# Sheet2.net
KiCad netlist of a schematic drawn in Altium Designer
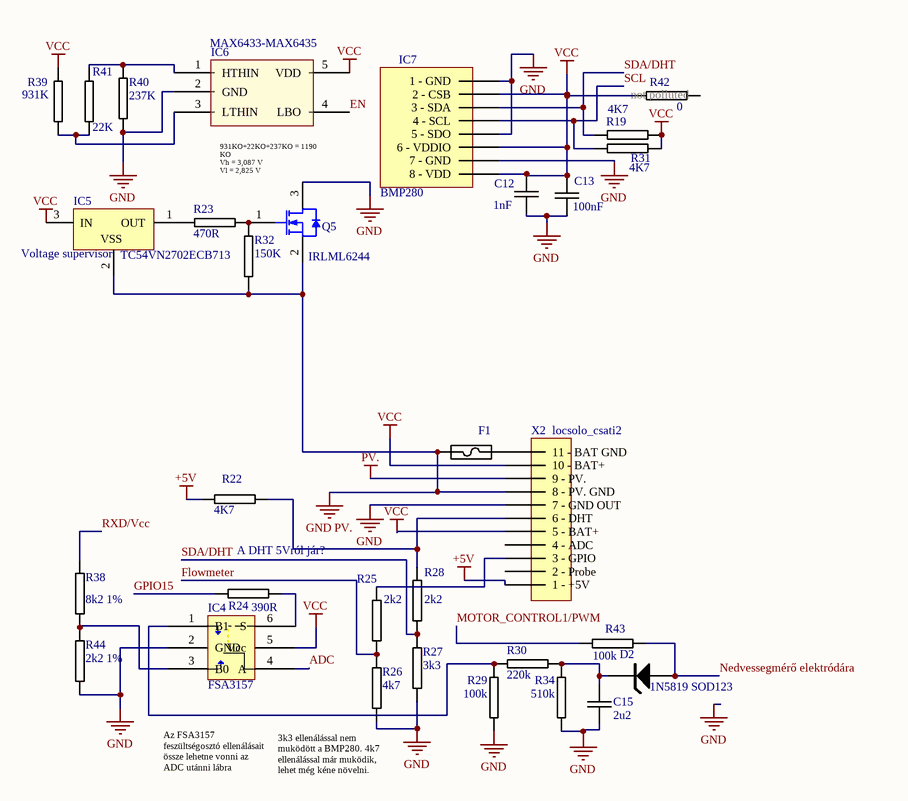
[diagram p0: Sheet2.SchDoc]

(export (version "E")
  (design (tool "Eeschema 10.0.6"))
  (components
    (comp (ref "C12")
      (value "1nF")
      (footprint "0805C-GENERIC")
      (description "100nF")
      (libsource (lib "vh_altium_library") (part "C0805-GENERIC"))
    )
    (comp (ref "C13")
      (value "100nF")
      (footprint "0805C-GENERIC")
      (libsource (lib "vh_altium_library") (part "C0805-GENERIC"))
    )
    (comp (ref "C15")
      (value "2u2")
      (footprint "0805C-GENERIC")
      (description "CAPACITOR 0805 CERAMIC")
      (fields
        (field (name "MANUFACTURER PART NUMBER") "ECJ-1VB0J225K")
        (field (name "MANUFACTURER") "Panasonic - ECG")
      )
      (libsource (lib "vh_altium_library") (part "0805C-2U2-6V3-X5R-PAN"))
    )
    (comp (ref "D2")
      (value "1N5819 SOD123")
      (footprint "sod-123")
      (description "DIODE / DIODE-B")
      (libsource (lib "vh_altium_library") (part "BZT52C5V6"))
    )
    (comp (ref "F1") (value "~") (footprint "Fuse_1206") (libsource (lib "Fuse_1206") (part "Fuse")))
    (comp (ref "IC4") (value "FSA3157") (footprint "SC70-6") (libsource (lib "components") (part "FSA3157")))
    (comp (ref "IC5")
      (value "TC54VN2702ECB713")
      (footprint "SOT-23A-CB3_L")
      (fields (field (name "PUBLISHER") "Altium Limited"))
      (libsource (lib "Microchip Power Mgt Voltage Detector") (part "TC54VN2702ECB713"))
    )
    (comp (ref "IC6")
      (value "MAX6433-MAX6435")
      (footprint "SOT23-5")
      (libsource (lib "components") (part "MAX6433-MAX6435"))
    )
    (comp (ref "IC7") (value "BMP280") (footprint "BMP280") (libsource (lib "components") (part "BMP280")))
    (comp (ref "Q5")
      (value "IRLML6244")
      (footprint "INF-PG-SOT23_N")
      (fields (field (name "MANUFACTURER") "Infineon") (field (name "PARTNUMBER") "BSS806N"))
      (libsource (lib "Infineon_Power_MOSFET") (part "BSS806N"))
    )
    (comp (ref "R19")
      (value "4K7")
      (footprint "0805R-4K7")
      (description "RESISTOR 0805 1/4 WATT THIN FILM")
      (libsource (lib "vh_altium_library") (part "0805R-4K7"))
    )
    (comp (ref "R22")
      (value "4K7")
      (footprint "0805R-4K7")
      (description "RESISTOR 0805 1/4 WATT THIN FILM")
      (libsource (lib "vh_altium_library") (part "0805R-4K7"))
    )
    (comp (ref "R23")
      (value "470R")
      (footprint "0805R-470")
      (description "RESISTOR 0805 1/4 WATT THIN FILM")
      (libsource (lib "vh_altium_library") (part "0805R-470"))
    )
    (comp (ref "R24")
      (value "390R")
      (footprint "0805R-390")
      (description "RESISTOR 0805 1/4 WATT THIN FILM")
      (libsource (lib "vh_altium_library") (part "0805R-390"))
    )
    (comp (ref "R25")
      (value "2k2")
      (footprint "0805R-4K7")
      (description "RESISTOR 0805 1/4 WATT THIN FILM")
      (libsource (lib "vh_altium_library") (part "0805R-4K7"))
    )
    (comp (ref "R26")
      (value "4k7")
      (footprint "0805R-4K7")
      (description "RESISTOR 0805 1/4 WATT THIN FILM")
      (libsource (lib "vh_altium_library") (part "0805R-4K7"))
    )
    (comp (ref "R27")
      (value "3k3")
      (footprint "0805R-4K7")
      (description "RESISTOR 0805 1/4 WATT THIN FILM")
      (libsource (lib "vh_altium_library") (part "0805R-4K7"))
    )
    (comp (ref "R28")
      (value "2k2")
      (footprint "0805R-4K7")
      (description "RESISTOR 0805 1/4 WATT THIN FILM")
      (libsource (lib "vh_altium_library") (part "0805R-4K7"))
    )
    (comp (ref "R29")
      (value "100k")
      (footprint "0805R-100")
      (description "RESISTOR 0805 1/4 WATT THIN FILM")
      (libsource (lib "vh_altium_library") (part "0805R-100"))
    )
    (comp (ref "R30")
      (value "220k")
      (footprint "0805R-100")
      (description "RESISTOR 0805 1/4 WATT THIN FILM")
      (libsource (lib "vh_altium_library") (part "0805R-100"))
    )
    (comp (ref "R31")
      (value "4K7")
      (footprint "0805R-4K7")
      (description "RESISTOR 0805 1/4 WATT THIN FILM")
      (libsource (lib "vh_altium_library") (part "0805R-4K7"))
    )
    (comp (ref "R32")
      (value "150K")
      (footprint "0805R-150K")
      (description "RESISTOR 0805 1/4 WATT THIN FILM")
      (libsource (lib "vh_altium_library") (part "0805R-150K"))
    )
    (comp (ref "R34")
      (value "510k")
      (footprint "0805R-100")
      (description "RESISTOR 0805 1/4 WATT THIN FILM")
      (libsource (lib "vh_altium_library") (part "0805R-100"))
    )
    (comp (ref "R38")
      (value "8k2 1%")
      (footprint "0805R-4K7")
      (description "RESISTOR 0805 1/4 WATT THIN FILM")
      (libsource (lib "vh_altium_library") (part "0805R-4K7"))
    )
    (comp (ref "R39")
      (value "931K")
      (footprint "0805R-TBD")
      (description "RESISTOR 0805 VALUE TO BE DETERMINED")
      (libsource (lib "vh_altium_library") (part "0805R-TBD"))
    )
    (comp (ref "R40")
      (value "237K")
      (footprint "0805R-TBD")
      (description "RESISTOR 0805 VALUE TO BE DETERMINED")
      (libsource (lib "vh_altium_library") (part "0805R-TBD"))
    )
    (comp (ref "R41")
      (value "22K")
      (footprint "0805R-TBD")
      (description "RESISTOR 0805 VALUE TO BE DETERMINED")
      (libsource (lib "vh_altium_library") (part "0805R-TBD"))
    )
    (comp (ref "R42")
      (value "0")
      (footprint "0805R-TBD")
      (description "RESISTOR 0805 VALUE TO BE DETERMINED")
      (libsource (lib "vh_altium_library") (part "0805R-TBD"))
    )
    (comp (ref "R43")
      (value "100k")
      (footprint "0805R-100")
      (description "RESISTOR 0805 1/4 WATT THIN FILM")
      (libsource (lib "vh_altium_library") (part "0805R-100"))
    )
    (comp (ref "R44")
      (value "2k2 1%")
      (footprint "0805R-1K")
      (description "RESISTOR 0805 1/4 WATT THIN FILM")
      (libsource (lib "vh_altium_library") (part "0805R-1K"))
    )
    (comp (ref "X2")
      (value "locsolo_csati2")
      (footprint "locsolo_csati2")
      (libsource (lib "components") (part "locsolo_csati2"))
    )
  )
  (nets
    (net (code "1") (name "+5V") (class "Default")
      (node (ref "R22") (pin "1") (pintype "passive"))
      (node (ref "X2") (pin "1") (pinfunction "1_-_+5V_1") (pintype "passive"))
    )
    (net (code "2") (name "/ADC") (class "Default")
      (node (ref "IC4") (pin "4") (pinfunction "A_4") (pintype "passive"))
    )
    (net (code "3") (name "/EN") (class "Default")
      (node (ref "IC6") (pin "4") (pinfunction "LBO_4") (pintype "passive"))
    )
    (net (code "4") (name "/Flowmeter") (class "Default")
      (node (ref "R25") (pin "1") (pintype "passive"))
      (node (ref "R26") (pin "2") (pintype "passive"))
    )
    (net (code "5") (name "/GPIO15") (class "Default") (node (ref "R24") (pin "1") (pintype "passive")))
    (net (code "6") (name "/MOTOR_CONTROL1{slash}PWM") (class "Default")
      (node (ref "R43") (pin "1") (pintype "passive"))
    )
    (net (code "7") (name "/Nedvessegmérő elektródára") (class "Default")
      (node (ref "D2") (pin "A") (pinfunction "A_A") (pintype "passive"))
      (node (ref "R43") (pin "2") (pintype "passive"))
    )
    (net (code "8") (name "/RXD{slash}Vcc") (class "Default")
      (node (ref "R38") (pin "1") (pintype "passive"))
    )
    (net (code "9") (name "/SCL") (class "Default")
      (node (ref "IC7") (pin "4") (pinfunction "4_-_SCL_4") (pintype "passive"))
      (node (ref "R31") (pin "1") (pintype "passive"))
    )
    (net (code "10") (name "/SDA{slash}DHT") (class "Default")
      (node (ref "IC7") (pin "3") (pinfunction "3_-_SDA_3") (pintype "passive"))
      (node (ref "R19") (pin "1") (pintype "passive"))
      (node (ref "R27") (pin "2") (pintype "passive"))
      (node (ref "R28") (pin "1") (pintype "passive"))
    )
    (net (code "11") (name "GND") (class "Default")
      (node (ref "C12") (pin "2") (pintype "passive"))
      (node (ref "C13") (pin "2") (pintype "passive"))
      (node (ref "C15") (pin "2") (pintype "passive"))
      (node (ref "IC4") (pin "2") (pinfunction "GND_2") (pintype "passive"))
      (node (ref "IC6") (pin "2") (pinfunction "GND_2") (pintype "passive"))
      (node (ref "IC7") (pin "1") (pinfunction "1_-_GND_1") (pintype "passive"))
      (node (ref "IC7") (pin "5") (pinfunction "5_-_SDO_5") (pintype "passive"))
      (node (ref "IC7") (pin "7") (pinfunction "7_-_GND_7") (pintype "passive"))
      (node (ref "Q5") (pin "3") (pinfunction "DRAIN_3") (pintype "passive"))
      (node (ref "R26") (pin "1") (pintype "passive"))
      (node (ref "R27") (pin "1") (pintype "passive"))
      (node (ref "R29") (pin "1") (pintype "passive"))
      (node (ref "R34") (pin "1") (pintype "passive"))
      (node (ref "R40") (pin "2") (pintype "passive"))
      (node (ref "R44") (pin "1") (pintype "passive"))
      (node (ref "X2") (pin "7") (pinfunction "7_-_GND_OUT_7") (pintype "passive"))
    )
    (net (code "12") (name "GND PV.") (class "Default")
      (node (ref "F1") (pin "1") (pintype "passive"))
      (node (ref "IC5") (pin "2") (pinfunction "VSS_2") (pintype "power_in"))
      (node (ref "Q5") (pin "2") (pinfunction "SOURCE_2") (pintype "passive"))
      (node (ref "R32") (pin "2") (pintype "passive"))
      (node (ref "X2") (pin "8") (pinfunction "8_-_PV._GND_8") (pintype "passive"))
    )
    (net (code "13") (name "Net-(C15-Pad1)") (class "Default")
      (node (ref "C15") (pin "1") (pintype "passive"))
      (node (ref "D2") (pin "K") (pinfunction "K_K") (pintype "passive"))
      (node (ref "R30") (pin "1") (pintype "passive"))
      (node (ref "R34") (pin "2") (pintype "passive"))
    )
    (net (code "14") (name "Net-(IC4-B0)") (class "Default")
      (node (ref "IC4") (pin "3") (pinfunction "B0_3") (pintype "passive"))
      (node (ref "R38") (pin "2") (pintype "passive"))
      (node (ref "R44") (pin "2") (pintype "passive"))
    )
    (net (code "15") (name "Net-(IC4-B1)") (class "Default")
      (node (ref "IC4") (pin "1") (pinfunction "B1_1") (pintype "passive"))
      (node (ref "R29") (pin "2") (pintype "passive"))
      (node (ref "R30") (pin "2") (pintype "passive"))
    )
    (net (code "16") (name "Net-(IC4-S)") (class "Default")
      (node (ref "IC4") (pin "6") (pinfunction "S_6") (pintype "passive"))
      (node (ref "R24") (pin "2") (pintype "passive"))
    )
    (net (code "17") (name "Net-(IC5-OUT)") (class "Default")
      (node (ref "IC5") (pin "1") (pinfunction "OUT_1") (pintype "power_in"))
      (node (ref "R23") (pin "1") (pintype "passive"))
    )
    (net (code "18") (name "Net-(IC6-HTHIN)") (class "Default")
      (node (ref "IC6") (pin "1") (pinfunction "HTHIN_1") (pintype "passive"))
      (node (ref "R40") (pin "1") (pintype "passive"))
      (node (ref "R41") (pin "2") (pintype "passive"))
    )
    (net (code "19") (name "Net-(IC6-LTHIN)") (class "Default")
      (node (ref "IC6") (pin "3") (pinfunction "LTHIN_3") (pintype "passive"))
      (node (ref "R39") (pin "1") (pintype "passive"))
      (node (ref "R41") (pin "1") (pintype "passive"))
    )
    (net (code "20") (name "Net-(Q5-GATE)") (class "Default")
      (node (ref "Q5") (pin "1") (pinfunction "GATE_1") (pintype "passive"))
      (node (ref "R23") (pin "2") (pintype "passive"))
      (node (ref "R32") (pin "1") (pintype "passive"))
    )
    (net (code "21") (name "Net-(X2-3_-_GPIO)") (class "Default")
      (node (ref "R25") (pin "2") (pintype "passive"))
      (node (ref "X2") (pin "3") (pinfunction "3_-_GPIO_3") (pintype "passive"))
    )
    (net (code "22") (name "Net-(X2-6_-_DHT)") (class "Default")
      (node (ref "R22") (pin "2") (pintype "passive"))
      (node (ref "R28") (pin "2") (pintype "passive"))
      (node (ref "X2") (pin "6") (pinfunction "6_-_DHT_6") (pintype "passive"))
    )
    (net (code "23") (name "Net-(X2-11_-_BAT_GND)") (class "Default")
      (node (ref "F1") (pin "2") (pintype "passive"))
      (node (ref "X2") (pin "11") (pinfunction "11_-_BAT_GND_11") (pintype "passive"))
    )
    (net (code "24") (name "PV.") (class "Default")
      (node (ref "X2") (pin "9") (pinfunction "9_-_PV._9") (pintype "passive"))
    )
    (net (code "25") (name "VCC") (class "Default")
      (node (ref "C12") (pin "1") (pintype "passive"))
      (node (ref "C13") (pin "1") (pintype "passive"))
      (node (ref "IC4") (pin "5") (pinfunction "Vcc_5") (pintype "passive"))
      (node (ref "IC5") (pin "3") (pinfunction "IN_3") (pintype "power_in"))
      (node (ref "IC6") (pin "5") (pinfunction "VDD_5") (pintype "passive"))
      (node (ref "IC7") (pin "2") (pinfunction "2_-_CSB_2") (pintype "passive"))
      (node (ref "IC7") (pin "6") (pinfunction "6_-_VDDIO_6") (pintype "passive"))
      (node (ref "IC7") (pin "8") (pinfunction "8_-_VDD_8") (pintype "passive"))
      (node (ref "R19") (pin "2") (pintype "passive"))
      (node (ref "R31") (pin "2") (pintype "passive"))
      (node (ref "R39") (pin "2") (pintype "passive"))
      (node (ref "R42") (pin "1") (pintype "passive"))
      (node (ref "X2") (pin "10") (pinfunction "10_-_BAT+_10") (pintype "passive"))
      (node (ref "X2") (pin "5") (pinfunction "5_-_BAT+_5") (pintype "passive"))
    )
    (net (code "26") (name "unconnected-(R42-Pad2)") (class "Default")
      (node (ref "R42") (pin "2") (pintype "passive"))
    )
    (net (code "27") (name "unconnected-(X2-2_-_Probe-Pad2)") (class "Default")
      (node (ref "X2") (pin "2") (pinfunction "2_-_Probe_2") (pintype "passive"))
    )
    (net (code "28") (name "unconnected-(X2-4_-_ADC-Pad4)") (class "Default")
      (node (ref "X2") (pin "4") (pinfunction "4_-_ADC_4") (pintype "passive"))
    )
  )
)
